# LightRetaggioSchema_v2.net
KiCad netlist of a schematic drawn in EAGLE
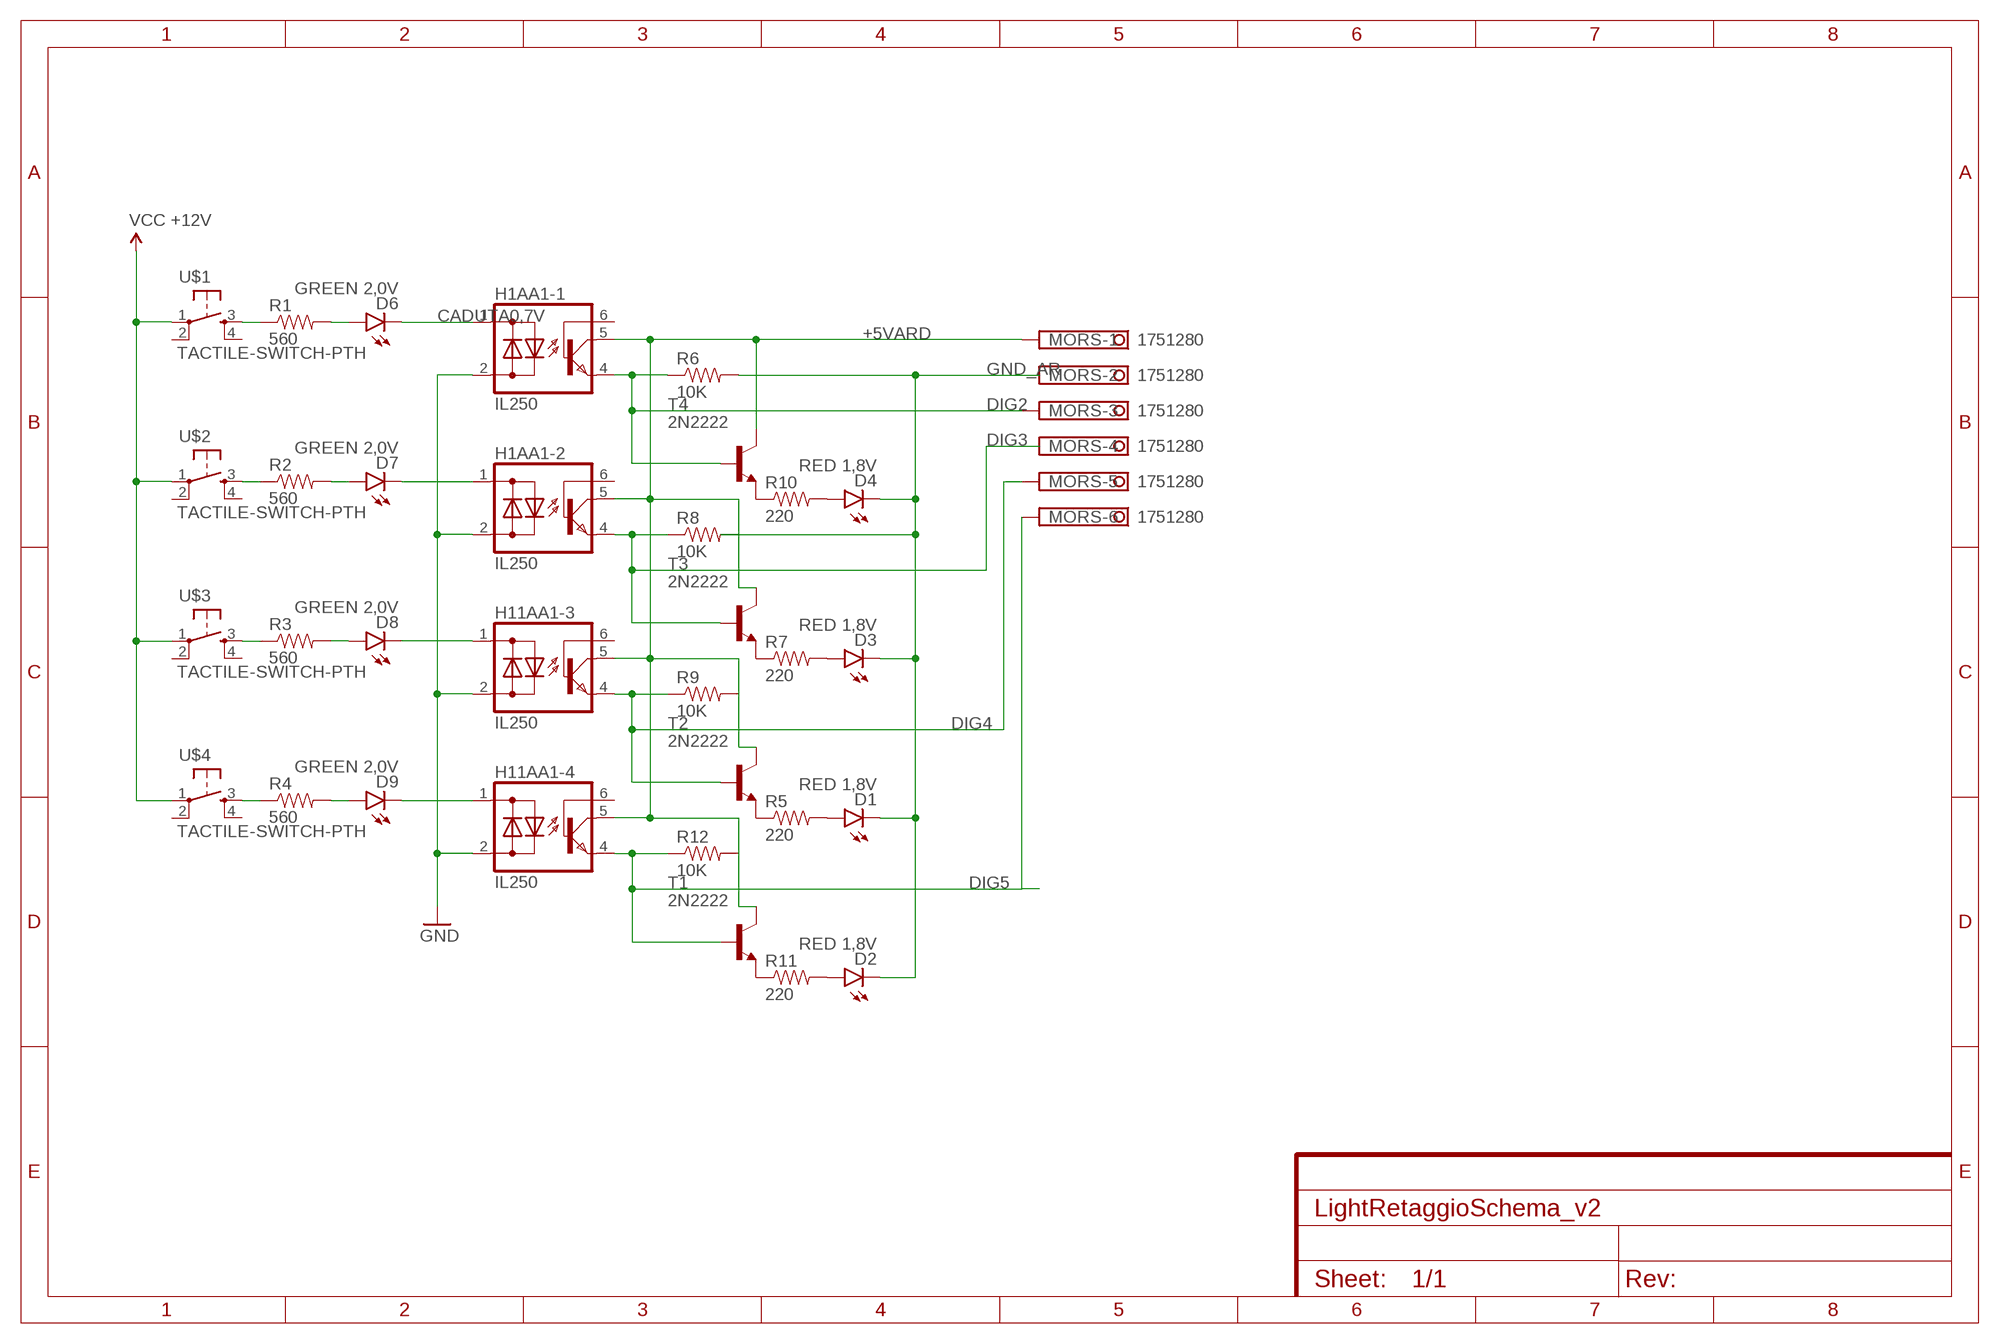
[diagram p0: schematic, sheet 1]

(export (version "E")
  (design (tool "Eeschema 10.0.6"))
  (components
    (comp (ref "D1")
      (value "RED 1,8V")
      (footprint "eagle-import:LED-1206")
      (libsource (lib "eagle-import") (part "LED-RED1206"))
    )
    (comp (ref "D2")
      (value "RED 1,8V")
      (footprint "eagle-import:LED-1206")
      (libsource (lib "eagle-import") (part "LED-RED1206"))
    )
    (comp (ref "D3")
      (value "RED 1,8V")
      (footprint "eagle-import:LED-1206")
      (libsource (lib "eagle-import") (part "LED-RED1206"))
    )
    (comp (ref "D4")
      (value "RED 1,8V")
      (footprint "eagle-import:LED-1206")
      (libsource (lib "eagle-import") (part "LED-RED1206"))
    )
    (comp (ref "D6")
      (value "GREEN 2,0V")
      (footprint "eagle-import:LED-1206")
      (libsource (lib "eagle-import") (part "LED-RED1206"))
    )
    (comp (ref "D7")
      (value "GREEN 2,0V")
      (footprint "eagle-import:LED-1206")
      (libsource (lib "eagle-import") (part "LED-RED1206"))
    )
    (comp (ref "D8")
      (value "GREEN 2,0V")
      (footprint "eagle-import:LED-1206")
      (libsource (lib "eagle-import") (part "LED-RED1206"))
    )
    (comp (ref "D9")
      (value "GREEN 2,0V")
      (footprint "eagle-import:LED-1206")
      (libsource (lib "eagle-import") (part "LED-RED1206"))
    )
    (comp (ref "H1AA1-1")
      (value "IL250")
      (footprint "eagle-import:DIL06")
      (fields (field (name "MF") "VISHAY/TELEFUNKEN"))
      (libsource (lib "eagle-import") (part "IL250"))
    )
    (comp (ref "H1AA1-2")
      (value "IL250")
      (footprint "eagle-import:DIL06")
      (fields (field (name "MF") "VISHAY/TELEFUNKEN"))
      (libsource (lib "eagle-import") (part "IL250"))
    )
    (comp (ref "H11AA1-3")
      (value "IL250")
      (footprint "eagle-import:DIL06")
      (fields (field (name "MF") "VISHAY/TELEFUNKEN"))
      (libsource (lib "eagle-import") (part "IL250"))
    )
    (comp (ref "H11AA1-4")
      (value "IL250")
      (footprint "eagle-import:DIL06")
      (fields (field (name "MF") "VISHAY/TELEFUNKEN"))
      (libsource (lib "eagle-import") (part "IL250"))
    )
    (comp (ref "MORS")
      (value "1751280")
      (footprint "eagle-import:1751280")
      (libsource (lib "eagle-import") (part "1751280"))
    )
    (comp (ref "R1")
      (value "560")
      (footprint "eagle-import:AXIAL-0.4")
      (libsource (lib "eagle-import") (part "RESISTORPTH-1/4W"))
    )
    (comp (ref "R2")
      (value "560")
      (footprint "eagle-import:AXIAL-0.4")
      (libsource (lib "eagle-import") (part "RESISTORPTH-1/4W"))
    )
    (comp (ref "R3")
      (value "560")
      (footprint "eagle-import:AXIAL-0.4")
      (libsource (lib "eagle-import") (part "RESISTORPTH-1/4W"))
    )
    (comp (ref "R4")
      (value "560")
      (footprint "eagle-import:AXIAL-0.4")
      (libsource (lib "eagle-import") (part "RESISTORPTH-1/4W"))
    )
    (comp (ref "R5")
      (value "220")
      (footprint "eagle-import:AXIAL-0.4")
      (libsource (lib "eagle-import") (part "RESISTORPTH-1/4W"))
    )
    (comp (ref "R6")
      (value "10K")
      (footprint "eagle-import:AXIAL-0.4")
      (libsource (lib "eagle-import") (part "RESISTORPTH-1/4W"))
    )
    (comp (ref "R7")
      (value "220")
      (footprint "eagle-import:AXIAL-0.4")
      (libsource (lib "eagle-import") (part "RESISTORPTH-1/4W"))
    )
    (comp (ref "R8")
      (value "10K")
      (footprint "eagle-import:AXIAL-0.4")
      (libsource (lib "eagle-import") (part "RESISTORPTH-1/4W"))
    )
    (comp (ref "R9")
      (value "10K")
      (footprint "eagle-import:AXIAL-0.4")
      (libsource (lib "eagle-import") (part "RESISTORPTH-1/4W"))
    )
    (comp (ref "R10")
      (value "220")
      (footprint "eagle-import:AXIAL-0.4")
      (libsource (lib "eagle-import") (part "RESISTORPTH-1/4W"))
    )
    (comp (ref "R11")
      (value "220")
      (footprint "eagle-import:AXIAL-0.4")
      (libsource (lib "eagle-import") (part "RESISTORPTH-1/4W"))
    )
    (comp (ref "R12")
      (value "10K")
      (footprint "eagle-import:AXIAL-0.4")
      (libsource (lib "eagle-import") (part "RESISTORPTH-1/4W"))
    )
    (comp (ref "T1")
      (value "2N2222")
      (footprint "eagle-import:TO18")
      (libsource (lib "eagle-import") (part "2N2222"))
    )
    (comp (ref "T2")
      (value "2N2222")
      (footprint "eagle-import:TO18")
      (libsource (lib "eagle-import") (part "2N2222"))
    )
    (comp (ref "T3")
      (value "2N2222")
      (footprint "eagle-import:TO18")
      (libsource (lib "eagle-import") (part "2N2222"))
    )
    (comp (ref "T4")
      (value "2N2222")
      (footprint "eagle-import:TO18")
      (libsource (lib "eagle-import") (part "2N2222"))
    )
    (comp (ref "U$1")
      (value "TACTILE-SWITCH-PTH")
      (footprint "eagle-import:TAC-SWITCH-PTH")
      (libsource (lib "eagle-import") (part "TACTILE-SWITCH-PTH"))
    )
    (comp (ref "U$2")
      (value "TACTILE-SWITCH-PTH")
      (footprint "eagle-import:TAC-SWITCH-PTH")
      (libsource (lib "eagle-import") (part "TACTILE-SWITCH-PTH"))
    )
    (comp (ref "U$3")
      (value "TACTILE-SWITCH-PTH")
      (footprint "eagle-import:TAC-SWITCH-PTH")
      (libsource (lib "eagle-import") (part "TACTILE-SWITCH-PTH"))
    )
    (comp (ref "U$4")
      (value "TACTILE-SWITCH-PTH")
      (footprint "eagle-import:TAC-SWITCH-PTH")
      (libsource (lib "eagle-import") (part "TACTILE-SWITCH-PTH"))
    )
  )
  (nets
    (net (code "1") (name "/+5VARD") (class "Default")
      (node (ref "H11AA1-3") (pin "5") (pinfunction "C_5") (pintype "passive"))
      (node (ref "H11AA1-4") (pin "5") (pinfunction "C_5") (pintype "passive"))
      (node (ref "H1AA1-1") (pin "5") (pinfunction "C_5") (pintype "passive"))
      (node (ref "H1AA1-2") (pin "5") (pinfunction "C_5") (pintype "passive"))
      (node (ref "MORS") (pin "1") (pinfunction "K_1") (pintype "passive"))
      (node (ref "T1") (pin "3") (pinfunction "C_3") (pintype "passive"))
      (node (ref "T2") (pin "3") (pinfunction "C_3") (pintype "passive"))
      (node (ref "T3") (pin "3") (pinfunction "C_3") (pintype "passive"))
      (node (ref "T4") (pin "3") (pinfunction "C_3") (pintype "passive"))
    )
    (net (code "2") (name "/CADUTA0,7V") (class "Default")
      (node (ref "D6") (pin "C") (pinfunction "C_C") (pintype "passive"))
      (node (ref "H1AA1-1") (pin "1") (pinfunction "AC1_1") (pintype "passive"))
    )
    (net (code "3") (name "/DIG2") (class "Default")
      (node (ref "H1AA1-1") (pin "4") (pinfunction "E_4") (pintype "passive"))
      (node (ref "MORS") (pin "3") (pinfunction "K_3") (pintype "passive"))
      (node (ref "R6") (pin "P$1") (pinfunction "1_P$1") (pintype "passive"))
      (node (ref "T4") (pin "2") (pinfunction "B_2") (pintype "passive"))
    )
    (net (code "4") (name "/DIG3") (class "Default")
      (node (ref "H1AA1-2") (pin "4") (pinfunction "E_4") (pintype "passive"))
      (node (ref "R8") (pin "P$1") (pinfunction "1_P$1") (pintype "passive"))
      (node (ref "T3") (pin "2") (pinfunction "B_2") (pintype "passive"))
    )
    (net (code "5") (name "/DIG4") (class "Default")
      (node (ref "H11AA1-3") (pin "4") (pinfunction "E_4") (pintype "passive"))
      (node (ref "MORS") (pin "5") (pinfunction "K_5") (pintype "passive"))
      (node (ref "R9") (pin "P$1") (pinfunction "1_P$1") (pintype "passive"))
      (node (ref "T2") (pin "2") (pinfunction "B_2") (pintype "passive"))
    )
    (net (code "6") (name "/DIG5") (class "Default")
      (node (ref "H11AA1-4") (pin "4") (pinfunction "E_4") (pintype "passive"))
      (node (ref "MORS") (pin "6") (pinfunction "K_6") (pintype "passive"))
      (node (ref "R12") (pin "P$1") (pinfunction "1_P$1") (pintype "passive"))
      (node (ref "T1") (pin "2") (pinfunction "B_2") (pintype "passive"))
    )
    (net (code "7") (name "/GND_AR") (class "Default")
      (node (ref "D1") (pin "C") (pinfunction "C_C") (pintype "passive"))
      (node (ref "D2") (pin "C") (pinfunction "C_C") (pintype "passive"))
      (node (ref "D3") (pin "C") (pinfunction "C_C") (pintype "passive"))
      (node (ref "D4") (pin "C") (pinfunction "C_C") (pintype "passive"))
      (node (ref "R6") (pin "P$2") (pinfunction "2_P$2") (pintype "passive"))
    )
    (net (code "8") (name "GND") (class "Default")
      (node (ref "H11AA1-3") (pin "2") (pinfunction "AC2_2") (pintype "passive"))
      (node (ref "H11AA1-4") (pin "2") (pinfunction "AC2_2") (pintype "passive"))
      (node (ref "H1AA1-1") (pin "2") (pinfunction "AC2_2") (pintype "passive"))
      (node (ref "H1AA1-2") (pin "2") (pinfunction "AC2_2") (pintype "passive"))
    )
    (net (code "9") (name "Net-(H1AA1-2-AC1)") (class "Default")
      (node (ref "D7") (pin "C") (pinfunction "C_C") (pintype "passive"))
      (node (ref "H1AA1-2") (pin "1") (pinfunction "AC1_1") (pintype "passive"))
    )
    (net (code "10") (name "Net-(H11AA1-3-AC1)") (class "Default")
      (node (ref "D8") (pin "C") (pinfunction "C_C") (pintype "passive"))
      (node (ref "H11AA1-3") (pin "1") (pinfunction "AC1_1") (pintype "passive"))
    )
    (net (code "11") (name "Net-(H11AA1-4-AC1)") (class "Default")
      (node (ref "D9") (pin "C") (pinfunction "C_C") (pintype "passive"))
      (node (ref "H11AA1-4") (pin "1") (pinfunction "AC1_1") (pintype "passive"))
    )
    (net (code "12") (name "Net-(R1-1)") (class "Default")
      (node (ref "R1") (pin "P$1") (pinfunction "1_P$1") (pintype "passive"))
      (node (ref "U$1") (pin "3") (pinfunction "3_3") (pintype "passive"))
    )
    (net (code "13") (name "Net-(R1-2)") (class "Default")
      (node (ref "D6") (pin "A") (pinfunction "A_A") (pintype "passive"))
      (node (ref "R1") (pin "P$2") (pinfunction "2_P$2") (pintype "passive"))
    )
    (net (code "14") (name "Net-(R2-1)") (class "Default")
      (node (ref "R2") (pin "P$1") (pinfunction "1_P$1") (pintype "passive"))
      (node (ref "U$2") (pin "3") (pinfunction "3_3") (pintype "passive"))
    )
    (net (code "15") (name "Net-(R2-2)") (class "Default")
      (node (ref "D7") (pin "A") (pinfunction "A_A") (pintype "passive"))
      (node (ref "R2") (pin "P$2") (pinfunction "2_P$2") (pintype "passive"))
    )
    (net (code "16") (name "Net-(R3-1)") (class "Default")
      (node (ref "R3") (pin "P$1") (pinfunction "1_P$1") (pintype "passive"))
      (node (ref "U$3") (pin "3") (pinfunction "3_3") (pintype "passive"))
    )
    (net (code "17") (name "Net-(R3-2)") (class "Default")
      (node (ref "D8") (pin "A") (pinfunction "A_A") (pintype "passive"))
      (node (ref "R3") (pin "P$2") (pinfunction "2_P$2") (pintype "passive"))
    )
    (net (code "18") (name "Net-(R4-1)") (class "Default")
      (node (ref "R4") (pin "P$1") (pinfunction "1_P$1") (pintype "passive"))
      (node (ref "U$4") (pin "3") (pinfunction "3_3") (pintype "passive"))
    )
    (net (code "19") (name "Net-(R4-2)") (class "Default")
      (node (ref "D9") (pin "A") (pinfunction "A_A") (pintype "passive"))
      (node (ref "R4") (pin "P$2") (pinfunction "2_P$2") (pintype "passive"))
    )
    (net (code "20") (name "Net-(R5-1)") (class "Default")
      (node (ref "R5") (pin "P$1") (pinfunction "1_P$1") (pintype "passive"))
      (node (ref "T2") (pin "1") (pinfunction "E_1") (pintype "passive"))
    )
    (net (code "21") (name "Net-(R5-2)") (class "Default")
      (node (ref "D1") (pin "A") (pinfunction "A_A") (pintype "passive"))
      (node (ref "R5") (pin "P$2") (pinfunction "2_P$2") (pintype "passive"))
    )
    (net (code "22") (name "Net-(R7-1)") (class "Default")
      (node (ref "R7") (pin "P$1") (pinfunction "1_P$1") (pintype "passive"))
      (node (ref "T3") (pin "1") (pinfunction "E_1") (pintype "passive"))
    )
    (net (code "23") (name "Net-(R7-2)") (class "Default")
      (node (ref "D3") (pin "A") (pinfunction "A_A") (pintype "passive"))
      (node (ref "R7") (pin "P$2") (pinfunction "2_P$2") (pintype "passive"))
    )
    (net (code "24") (name "Net-(R10-1)") (class "Default")
      (node (ref "R10") (pin "P$1") (pinfunction "1_P$1") (pintype "passive"))
      (node (ref "T4") (pin "1") (pinfunction "E_1") (pintype "passive"))
    )
    (net (code "25") (name "Net-(R10-2)") (class "Default")
      (node (ref "D4") (pin "A") (pinfunction "A_A") (pintype "passive"))
      (node (ref "R10") (pin "P$2") (pinfunction "2_P$2") (pintype "passive"))
    )
    (net (code "26") (name "Net-(R11-1)") (class "Default")
      (node (ref "R11") (pin "P$1") (pinfunction "1_P$1") (pintype "passive"))
      (node (ref "T1") (pin "1") (pinfunction "E_1") (pintype "passive"))
    )
    (net (code "27") (name "Net-(R11-2)") (class "Default")
      (node (ref "D2") (pin "A") (pinfunction "A_A") (pintype "passive"))
      (node (ref "R11") (pin "P$2") (pinfunction "2_P$2") (pintype "passive"))
    )
    (net (code "28") (name "VCC +12V") (class "Default")
      (node (ref "U$1") (pin "1") (pinfunction "1_1") (pintype "passive"))
      (node (ref "U$2") (pin "1") (pinfunction "1_1") (pintype "passive"))
      (node (ref "U$3") (pin "1") (pinfunction "1_1") (pintype "passive"))
      (node (ref "U$4") (pin "1") (pinfunction "1_1") (pintype "passive"))
    )
    (net (code "29") (name "unconnected-(H1AA1-1-B-Pad6)") (class "Default")
      (node (ref "H1AA1-1") (pin "6") (pinfunction "B_6") (pintype "passive"))
    )
    (net (code "30") (name "unconnected-(H1AA1-2-B-Pad6)") (class "Default")
      (node (ref "H1AA1-2") (pin "6") (pinfunction "B_6") (pintype "passive"))
    )
    (net (code "31") (name "unconnected-(H11AA1-3-B-Pad6)") (class "Default")
      (node (ref "H11AA1-3") (pin "6") (pinfunction "B_6") (pintype "passive"))
    )
    (net (code "32") (name "unconnected-(H11AA1-4-B-Pad6)") (class "Default")
      (node (ref "H11AA1-4") (pin "6") (pinfunction "B_6") (pintype "passive"))
    )
    (net (code "33") (name "unconnected-(MORSB-K-Pad2)") (class "Default")
      (node (ref "MORS") (pin "2") (pinfunction "K_2") (pintype "passive"))
    )
    (net (code "34") (name "unconnected-(MORSD-K-Pad4)") (class "Default")
      (node (ref "MORS") (pin "4") (pinfunction "K_4") (pintype "passive"))
    )
    (net (code "35") (name "unconnected-(R8-2-PadP$2)") (class "Default")
      (node (ref "R8") (pin "P$2") (pinfunction "2_P$2") (pintype "passive"))
    )
    (net (code "36") (name "unconnected-(R9-2-PadP$2)") (class "Default")
      (node (ref "R9") (pin "P$2") (pinfunction "2_P$2") (pintype "passive"))
    )
    (net (code "37") (name "unconnected-(R12-2-PadP$2)") (class "Default")
      (node (ref "R12") (pin "P$2") (pinfunction "2_P$2") (pintype "passive"))
    )
    (net (code "38") (name "unconnected-(U$1-Pad2)") (class "Default")
      (node (ref "U$1") (pin "2") (pinfunction "2_2") (pintype "passive"))
    )
    (net (code "39") (name "unconnected-(U$1-Pad4)") (class "Default")
      (node (ref "U$1") (pin "4") (pinfunction "4_4") (pintype "passive"))
    )
    (net (code "40") (name "unconnected-(U$2-Pad2)") (class "Default")
      (node (ref "U$2") (pin "2") (pinfunction "2_2") (pintype "passive"))
    )
    (net (code "41") (name "unconnected-(U$2-Pad4)") (class "Default")
      (node (ref "U$2") (pin "4") (pinfunction "4_4") (pintype "passive"))
    )
    (net (code "42") (name "unconnected-(U$3-Pad2)") (class "Default")
      (node (ref "U$3") (pin "2") (pinfunction "2_2") (pintype "passive"))
    )
    (net (code "43") (name "unconnected-(U$3-Pad4)") (class "Default")
      (node (ref "U$3") (pin "4") (pinfunction "4_4") (pintype "passive"))
    )
    (net (code "44") (name "unconnected-(U$4-Pad2)") (class "Default")
      (node (ref "U$4") (pin "2") (pinfunction "2_2") (pintype "passive"))
    )
    (net (code "45") (name "unconnected-(U$4-Pad4)") (class "Default")
      (node (ref "U$4") (pin "4") (pinfunction "4_4") (pintype "passive"))
    )
  )
)
